# LED_Controller_Wireless.net
KiCad netlist of a schematic drawn in Altium Designer
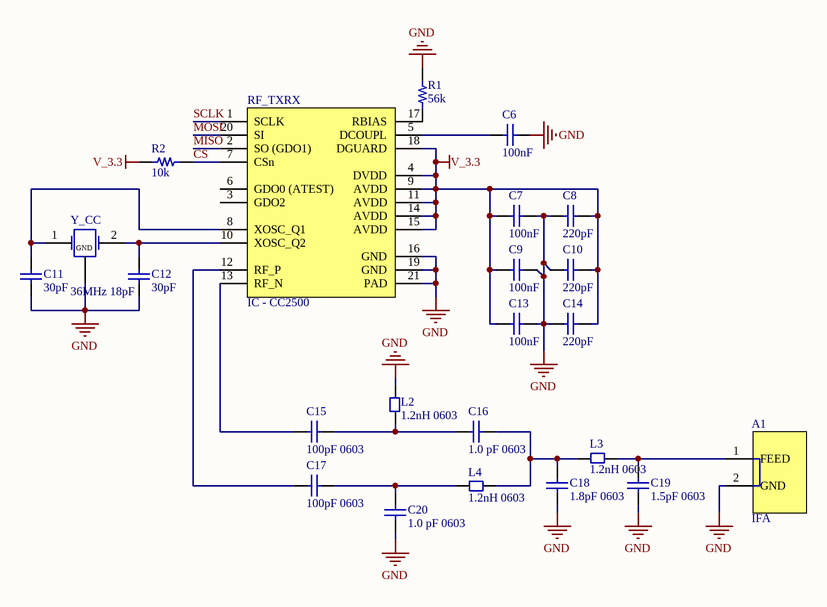
[diagram p0: LED_Controller_Wireless.SchDoc]

(export (version "E")
  (design (tool "Eeschema 10.0.6"))
  (components
    (comp (ref "A1")
      (value "IFA")
      (footprint "Meandered_Inverted_F_Antenna")
      (libsource (lib "My Schematic Library") (part "Meandered_Inverted_F_Antenna"))
    )
    (comp (ref "C6")
      (value "100nF")
      (footprint "0603")
      (description "CAP CER .10UF 50V X5R 0603")
      (fields
        (field (name "MANUFACTURER") "AVX Corporation")
        (field (name "MANUFACTURER PART NUMBER") "06035D104KAT2A")
      )
      (libsource (lib "My Schematic Library") (part "CP - 100nF 0603"))
    )
    (comp (ref "C7")
      (value "100nF")
      (footprint "0603")
      (description "CAP CER .10UF 50V X5R 0603")
      (fields
        (field (name "MANUFACTURER") "AVX Corporation")
        (field (name "MANUFACTURER PART NUMBER") "06035D104KAT2A")
      )
      (libsource (lib "My Schematic Library") (part "CP - 100nF 0603"))
    )
    (comp (ref "C8")
      (value "220pF")
      (footprint "0603")
      (description "CAP CER 220PF 50V NP0 0603")
      (fields
        (field (name "MANUFACTURER") "Johanson Dielectrics Inc")
        (field (name "MANUFACTURER PART NUMBER") "500R14N221JV4T")
      )
      (libsource (lib "My Schematic Library") (part "CP - 220pF 0603"))
    )
    (comp (ref "C9")
      (value "100nF")
      (footprint "0603")
      (description "CAP CER .10UF 50V X5R 0603")
      (fields
        (field (name "MANUFACTURER") "AVX Corporation")
        (field (name "MANUFACTURER PART NUMBER") "06035D104KAT2A")
      )
      (libsource (lib "My Schematic Library") (part "CP - 100nF 0603"))
    )
    (comp (ref "C10")
      (value "220pF")
      (footprint "0603")
      (description "CAP CER 220PF 50V NP0 0603")
      (fields
        (field (name "MANUFACTURER") "Johanson Dielectrics Inc")
        (field (name "MANUFACTURER PART NUMBER") "500R14N221JV4T")
      )
      (libsource (lib "My Schematic Library") (part "CP - 220pF 0603"))
    )
    (comp (ref "C11")
      (value "30pF")
      (footprint "0603")
      (description "CAP CER 30PF 50V C0G 0603")
      (fields
        (field (name "MANUFACTURER") "TDK Corporation")
        (field (name "MANUFACTURER PART NUMBER") "C1608C0G1H300J")
      )
      (libsource (lib "My Schematic Library") (part "CP - 30pF 0603"))
    )
    (comp (ref "C12")
      (value "30pF")
      (footprint "0603")
      (description "CAP CER 30PF 50V C0G 0603")
      (fields
        (field (name "MANUFACTURER") "TDK Corporation")
        (field (name "MANUFACTURER PART NUMBER") "C1608C0G1H300J")
      )
      (libsource (lib "My Schematic Library") (part "CP - 30pF 0603"))
    )
    (comp (ref "C13")
      (value "100nF")
      (footprint "0603")
      (description "CAP CER .10UF 50V X5R 0603")
      (fields
        (field (name "MANUFACTURER") "AVX Corporation")
        (field (name "MANUFACTURER PART NUMBER") "06035D104KAT2A")
      )
      (libsource (lib "My Schematic Library") (part "CP - 100nF 0603"))
    )
    (comp (ref "C14")
      (value "220pF")
      (footprint "0603")
      (description "CAP CER 220PF 50V NP0 0603")
      (fields
        (field (name "MANUFACTURER") "Johanson Dielectrics Inc")
        (field (name "MANUFACTURER PART NUMBER") "500R14N221JV4T")
      )
      (libsource (lib "My Schematic Library") (part "CP - 220pF 0603"))
    )
    (comp (ref "C15")
      (value "100pF 0603")
      (footprint "0603")
      (description "CAP CERM 100PF 5% 50V NP0 0603")
      (fields
        (field (name "MANUFACTURER") "AVX Corporation")
        (field (name "MANUFACTURER PART NUMBER") "06035A101JAT2A")
      )
      (libsource (lib "My Schematic Library") (part "CP - 100pF 0603"))
    )
    (comp (ref "C16")
      (value "1.0 pF 0603")
      (footprint "0603")
      (description "CAP CER 1.0PF 50V C0G 0603")
      (fields
        (field (name "MANUFACTURER") "TDK Corporation")
        (field (name "MANUFACTURER PART NUMBER") "C1608C0G1H010C")
      )
      (libsource (lib "My Schematic Library") (part "CP - 1.0pF 0603"))
    )
    (comp (ref "C17")
      (value "100pF 0603")
      (footprint "0603")
      (description "CAP CERM 100PF 5% 50V NP0 0603")
      (fields
        (field (name "MANUFACTURER") "AVX Corporation")
        (field (name "MANUFACTURER PART NUMBER") "06035A101JAT2A")
      )
      (libsource (lib "My Schematic Library") (part "CP - 100pF 0603"))
    )
    (comp (ref "C18")
      (value "1.8pF 0603")
      (footprint "0603")
      (description "CAP CER 1.8PF 50V C0G 0603")
      (fields
        (field (name "MANUFACTURER") "TDK Corporation")
        (field (name "MANUFACTURER PART NUMBER") "C1608C0G1H1R8C")
      )
      (libsource (lib "My Schematic Library") (part "CP - 1.8pF 0603"))
    )
    (comp (ref "C19")
      (value "1.5pF 0603")
      (footprint "0603")
      (description "CAP CER 1.5PF 50V C0G 0603")
      (fields
        (field (name "MANUFACTURER") "TDK Corporation")
        (field (name "MANUFACTURER PART NUMBER") "C1608C0G1H1R5C")
      )
      (libsource (lib "My Schematic Library") (part "CP - 1.5pF 0603"))
    )
    (comp (ref "C20")
      (value "1.0 pF 0603")
      (footprint "0603")
      (description "CAP CER 1.0PF 50V C0G 0603")
      (fields
        (field (name "MANUFACTURER") "TDK Corporation")
        (field (name "MANUFACTURER PART NUMBER") "C1608C0G1H010C")
      )
      (libsource (lib "My Schematic Library") (part "CP - 1.0pF 0603"))
    )
    (comp (ref "L2")
      (value "1.2nH 0603")
      (footprint "0603")
      (description "INDUCTOR HI FREQ 1.2+/-0.3NH")
      (fields
        (field (name "MANUFACTURER") "Taiyo Yuden")
        (field (name "MANUFACTURER PART NUMBER") "HK16081N2S-T")
      )
      (libsource (lib "My Schematic Library") (part "L - 1.2nH 0603"))
    )
    (comp (ref "L3")
      (value "1.2nH 0603")
      (footprint "0603")
      (description "INDUCTOR HI FREQ 1.2+/-0.3NH")
      (fields
        (field (name "MANUFACTURER") "Taiyo Yuden")
        (field (name "MANUFACTURER PART NUMBER") "HK16081N2S-T")
      )
      (libsource (lib "My Schematic Library") (part "L - 1.2nH 0603"))
    )
    (comp (ref "L4")
      (value "1.2nH 0603")
      (footprint "0603")
      (description "INDUCTOR HI FREQ 1.2+/-0.3NH")
      (fields
        (field (name "MANUFACTURER") "Taiyo Yuden")
        (field (name "MANUFACTURER PART NUMBER") "HK16081N2S-T")
      )
      (libsource (lib "My Schematic Library") (part "L - 1.2nH 0603"))
    )
    (comp (ref "R1")
      (value "56k")
      (footprint "0603")
      (description "RES 56K OHM 1/10W 5% 0603 SMD")
      (fields
        (field (name "MANUFACTURER") "Yageo")
        (field (name "MANUFACTURER PART NUMBER") "RC0603JR-0756KL")
      )
      (libsource (lib "My Schematic Library") (part "RS - 56k 0603"))
    )
    (comp (ref "R2")
      (value "10k")
      (footprint "0603")
      (description "RES 10.0K OHM 1/10W 1% 0603 SMD")
      (fields
        (field (name "MANUFACTURER") "Yageo")
        (field (name "MANUFACTURER PART NUMBER") "RC0603FR-0710KL")
      )
      (libsource (lib "My Schematic Library") (part "RS - 10k 0603"))
    )
    (comp (ref "RF_TXRX")
      (value "IC - CC2500")
      (footprint "TI - RTK / QFN50P400X400X90-20N")
      (description "IC RF TXRX SNGL-CHIP LP 20-QFN")
      (fields
        (field (name "MANUFACTURER") "Texas Instruments")
        (field (name "MANUFACTURER PART NUMBER") "CC2500RTKR")
      )
      (libsource (lib "My Schematic Library") (part "IC - CC2500"))
    )
    (comp (ref "Y_CC")
      (value "36MHz 18pF")
      (footprint "7M-36.000MAAJ-T")
      (description "CRYSTAL 36.000 MHZ 18PF SMD")
      (fields
        (field (name "MANUFACTURER") "TXC CORPORATION")
        (field (name "MANUFACTURER PART NUMBER") "7M-36.000MAAJ-T")
      )
      (libsource (lib "My Schematic Library") (part "X - 36MHz 18pF"))
    )
  )
  (nets
    (net (code "1") (name "/CS") (class "Default")
      (node (ref "R2") (pin "1") (pintype "passive"))
      (node (ref "RF_TXRX") (pin "7") (pinfunction "CSn_7") (pintype "passive"))
    )
    (net (code "2") (name "/MISO") (class "Default")
      (node (ref "RF_TXRX") (pin "2") (pinfunction "SO_(GDO1)_2") (pintype "passive"))
    )
    (net (code "3") (name "/MOSI") (class "Default")
      (node (ref "RF_TXRX") (pin "20") (pinfunction "SI_20") (pintype "passive"))
    )
    (net (code "4") (name "/SCLK") (class "Default")
      (node (ref "RF_TXRX") (pin "1") (pinfunction "SCLK_1") (pintype "passive"))
    )
    (net (code "5") (name "GND") (class "Default")
      (node (ref "A1") (pin "2") (pinfunction "GND_2") (pintype "passive"))
      (node (ref "C10") (pin "1") (pintype "passive"))
      (node (ref "C11") (pin "1") (pintype "passive"))
      (node (ref "C12") (pin "1") (pintype "passive"))
      (node (ref "C13") (pin "1") (pintype "passive"))
      (node (ref "C14") (pin "1") (pintype "passive"))
      (node (ref "C18") (pin "1") (pintype "passive"))
      (node (ref "C19") (pin "1") (pintype "passive"))
      (node (ref "C20") (pin "1") (pintype "passive"))
      (node (ref "C6") (pin "2") (pintype "passive"))
      (node (ref "C7") (pin "1") (pintype "passive"))
      (node (ref "C8") (pin "1") (pintype "passive"))
      (node (ref "C9") (pin "1") (pintype "passive"))
      (node (ref "L2") (pin "2") (pintype "passive"))
      (node (ref "R1") (pin "2") (pintype "passive"))
      (node (ref "RF_TXRX") (pin "16") (pinfunction "GND_16") (pintype "passive"))
      (node (ref "RF_TXRX") (pin "19") (pinfunction "GND_19") (pintype "passive"))
      (node (ref "RF_TXRX") (pin "21") (pinfunction "PAD_21") (pintype "passive"))
      (node (ref "Y_CC") (pin "3") (pinfunction "GND_3") (pintype "passive"))
    )
    (net (code "6") (name "Net-(A1-FEED)") (class "Default")
      (node (ref "A1") (pin "1") (pinfunction "FEED_1") (pintype "passive"))
      (node (ref "C19") (pin "2") (pintype "passive"))
      (node (ref "L3") (pin "2") (pintype "passive"))
    )
    (net (code "7") (name "Net-(C15-Pad2)") (class "Default")
      (node (ref "C15") (pin "2") (pintype "passive"))
      (node (ref "C16") (pin "1") (pintype "passive"))
      (node (ref "L2") (pin "1") (pintype "passive"))
    )
    (net (code "8") (name "Net-(C16-Pad2)") (class "Default")
      (node (ref "C16") (pin "2") (pintype "passive"))
      (node (ref "C18") (pin "2") (pintype "passive"))
      (node (ref "L3") (pin "1") (pintype "passive"))
      (node (ref "L4") (pin "1") (pintype "passive"))
    )
    (net (code "9") (name "Net-(C17-Pad2)") (class "Default")
      (node (ref "C17") (pin "2") (pintype "passive"))
      (node (ref "C20") (pin "2") (pintype "passive"))
      (node (ref "L4") (pin "2") (pintype "passive"))
    )
    (net (code "10") (name "Net-(RF_TXRX-DCOUPL)") (class "Default")
      (node (ref "C6") (pin "1") (pintype "passive"))
      (node (ref "RF_TXRX") (pin "5") (pinfunction "DCOUPL_5") (pintype "passive"))
    )
    (net (code "11") (name "Net-(RF_TXRX-RBIAS)") (class "Default")
      (node (ref "R1") (pin "1") (pintype "passive"))
      (node (ref "RF_TXRX") (pin "17") (pinfunction "RBIAS_17") (pintype "passive"))
    )
    (net (code "12") (name "Net-(RF_TXRX-RF_N)") (class "Default")
      (node (ref "C15") (pin "1") (pintype "passive"))
      (node (ref "RF_TXRX") (pin "13") (pinfunction "RF_N_13") (pintype "passive"))
    )
    (net (code "13") (name "Net-(RF_TXRX-RF_P)") (class "Default")
      (node (ref "C17") (pin "1") (pintype "passive"))
      (node (ref "RF_TXRX") (pin "12") (pinfunction "RF_P_12") (pintype "passive"))
    )
    (net (code "14") (name "Net-(RF_TXRX-XOSC_Q1)") (class "Default")
      (node (ref "C11") (pin "2") (pintype "passive"))
      (node (ref "RF_TXRX") (pin "8") (pinfunction "XOSC_Q1_8") (pintype "passive"))
      (node (ref "Y_CC") (pin "1") (pintype "passive"))
    )
    (net (code "15") (name "Net-(RF_TXRX-XOSC_Q2)") (class "Default")
      (node (ref "C12") (pin "2") (pintype "passive"))
      (node (ref "RF_TXRX") (pin "10") (pinfunction "XOSC_Q2_10") (pintype "passive"))
      (node (ref "Y_CC") (pin "2") (pintype "passive"))
    )
    (net (code "16") (name "V_3.3") (class "Default")
      (node (ref "C10") (pin "2") (pintype "passive"))
      (node (ref "C13") (pin "2") (pintype "passive"))
      (node (ref "C14") (pin "2") (pintype "passive"))
      (node (ref "C7") (pin "2") (pintype "passive"))
      (node (ref "C8") (pin "2") (pintype "passive"))
      (node (ref "C9") (pin "2") (pintype "passive"))
      (node (ref "R2") (pin "2") (pintype "passive"))
      (node (ref "RF_TXRX") (pin "11") (pinfunction "AVDD_11") (pintype "passive"))
      (node (ref "RF_TXRX") (pin "14") (pinfunction "AVDD_14") (pintype "passive"))
      (node (ref "RF_TXRX") (pin "15") (pinfunction "AVDD_15") (pintype "passive"))
      (node (ref "RF_TXRX") (pin "18") (pinfunction "DGUARD_18") (pintype "passive"))
      (node (ref "RF_TXRX") (pin "4") (pinfunction "DVDD_4") (pintype "passive"))
      (node (ref "RF_TXRX") (pin "9") (pinfunction "AVDD_9") (pintype "passive"))
    )
    (net (code "17") (name "unconnected-(RF_TXRX-GDO0_(ATEST)-Pad6)") (class "Default")
      (node (ref "RF_TXRX") (pin "6") (pinfunction "GDO0_(ATEST)_6") (pintype "passive"))
    )
    (net (code "18") (name "unconnected-(RF_TXRX-GDO2-Pad3)") (class "Default")
      (node (ref "RF_TXRX") (pin "3") (pinfunction "GDO2_3") (pintype "passive"))
    )
  )
)
